# dreamblaster.net
KiCad netlist of a schematic drawn in EAGLE
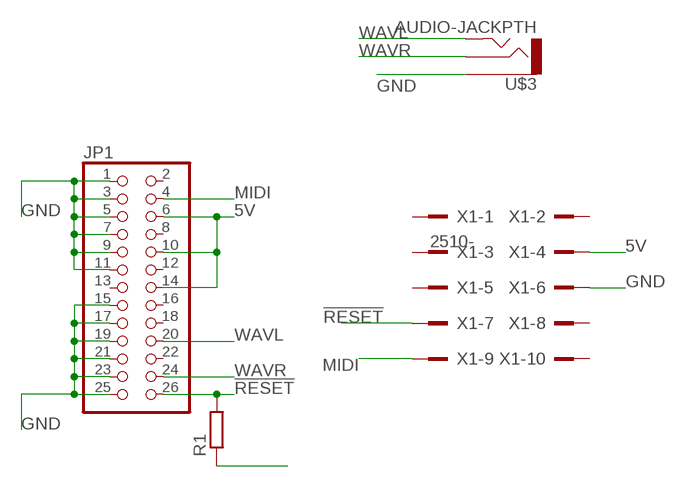
[diagram p0: schematic, sheet 1]

(export (version "E")
  (design (tool "Eeschema 10.0.6"))
  (components
    (comp (ref "JP1")
      (value "PINHD-2X13")
      (footprint "eagle-import:2X13")
      (libsource (lib "eagle-import") (part "PINHD-2X13"))
    )
    (comp (ref "R1")
      (value "R-EU_0204/7")
      (footprint "eagle-import:0204_7")
      (libsource (lib "eagle-import") (part "R-EU_0204/7"))
    )
    (comp (ref "U$3")
      (value "AUDIO-JACKPTH")
      (footprint "eagle-import:AUDIO-JACK")
      (libsource (lib "eagle-import") (part "AUDIO-JACKPTH"))
    )
    (comp (ref "X1")
      (value "2510-")
      (footprint "eagle-import:PAK100_2500-10")
      (fields (field (name "MF") "3M") (field (name "MPN") "2510-6002UB"))
      (libsource (lib "eagle-import") (part "2510-"))
    )
  )
  (nets
    (net (code "1") (name "/5V") (class "Default")
      (node (ref "JP1") (pin "10") (pinfunction "10_10") (pintype "passive"))
      (node (ref "JP1") (pin "14") (pinfunction "14_14") (pintype "passive"))
      (node (ref "JP1") (pin "6") (pinfunction "6_6") (pintype "passive"))
      (node (ref "R1") (pin "1") (pinfunction "1_1") (pintype "passive"))
      (node (ref "X1") (pin "4") (pinfunction "KL_4") (pintype "passive"))
    )
    (net (code "2") (name "/GND") (class "Default")
      (node (ref "JP1") (pin "1") (pinfunction "1_1") (pintype "passive"))
      (node (ref "JP1") (pin "11") (pinfunction "11_11") (pintype "passive"))
      (node (ref "JP1") (pin "15") (pinfunction "15_15") (pintype "passive"))
      (node (ref "JP1") (pin "17") (pinfunction "17_17") (pintype "passive"))
      (node (ref "JP1") (pin "19") (pinfunction "19_19") (pintype "passive"))
      (node (ref "JP1") (pin "21") (pinfunction "21_21") (pintype "passive"))
      (node (ref "JP1") (pin "23") (pinfunction "23_23") (pintype "passive"))
      (node (ref "JP1") (pin "25") (pinfunction "25_25") (pintype "passive"))
      (node (ref "JP1") (pin "3") (pinfunction "3_3") (pintype "passive"))
      (node (ref "JP1") (pin "5") (pinfunction "5_5") (pintype "passive"))
      (node (ref "JP1") (pin "7") (pinfunction "7_7") (pintype "passive"))
      (node (ref "JP1") (pin "9") (pinfunction "9_9") (pintype "passive"))
      (node (ref "U$3") (pin "1") (pinfunction "1_1") (pintype "bidirectional"))
      (node (ref "X1") (pin "6") (pinfunction "KL_6") (pintype "passive"))
    )
    (net (code "3") (name "/MIDI") (class "Default")
      (node (ref "JP1") (pin "4") (pinfunction "4_4") (pintype "passive"))
      (node (ref "X1") (pin "9") (pinfunction "KL_9") (pintype "passive"))
    )
    (net (code "4") (name "/WAVL") (class "Default")
      (node (ref "JP1") (pin "20") (pinfunction "20_20") (pintype "passive"))
      (node (ref "U$3") (pin "5") (pinfunction "5_5") (pintype "bidirectional"))
    )
    (net (code "5") (name "/WAVR") (class "Default")
      (node (ref "JP1") (pin "24") (pinfunction "24_24") (pintype "passive"))
      (node (ref "U$3") (pin "2") (pinfunction "2_2") (pintype "bidirectional"))
    )
    (net (code "6") (name "/~{RESET}") (class "Default")
      (node (ref "JP1") (pin "26") (pinfunction "26_26") (pintype "passive"))
      (node (ref "R1") (pin "2") (pinfunction "2_2") (pintype "passive"))
      (node (ref "X1") (pin "7") (pinfunction "KL_7") (pintype "passive"))
    )
    (net (code "7") (name "unconnected-(JP1-Pad2)") (class "Default")
      (node (ref "JP1") (pin "2") (pinfunction "2_2") (pintype "passive"))
    )
    (net (code "8") (name "unconnected-(JP1-Pad8)") (class "Default")
      (node (ref "JP1") (pin "8") (pinfunction "8_8") (pintype "passive"))
    )
    (net (code "9") (name "unconnected-(JP1-Pad12)") (class "Default")
      (node (ref "JP1") (pin "12") (pinfunction "12_12") (pintype "passive"))
    )
    (net (code "10") (name "unconnected-(JP1-Pad13)") (class "Default")
      (node (ref "JP1") (pin "13") (pinfunction "13_13") (pintype "passive"))
    )
    (net (code "11") (name "unconnected-(JP1-Pad16)") (class "Default")
      (node (ref "JP1") (pin "16") (pinfunction "16_16") (pintype "passive"))
    )
    (net (code "12") (name "unconnected-(JP1-Pad18)") (class "Default")
      (node (ref "JP1") (pin "18") (pinfunction "18_18") (pintype "passive"))
    )
    (net (code "13") (name "unconnected-(JP1-Pad22)") (class "Default")
      (node (ref "JP1") (pin "22") (pinfunction "22_22") (pintype "passive"))
    )
    (net (code "14") (name "unconnected-(X1A-KL-Pad1)") (class "Default")
      (node (ref "X1") (pin "1") (pinfunction "KL_1") (pintype "passive"))
    )
    (net (code "15") (name "unconnected-(X1B-KL-Pad10)") (class "Default")
      (node (ref "X1") (pin "10") (pinfunction "KL_10") (pintype "passive"))
    )
    (net (code "16") (name "unconnected-(X1C-KL-Pad2)") (class "Default")
      (node (ref "X1") (pin "2") (pinfunction "KL_2") (pintype "passive"))
    )
    (net (code "17") (name "unconnected-(X1D-KL-Pad3)") (class "Default")
      (node (ref "X1") (pin "3") (pinfunction "KL_3") (pintype "passive"))
    )
    (net (code "18") (name "unconnected-(X1F-KL-Pad5)") (class "Default")
      (node (ref "X1") (pin "5") (pinfunction "KL_5") (pintype "passive"))
    )
    (net (code "19") (name "unconnected-(X1I-KL-Pad8)") (class "Default")
      (node (ref "X1") (pin "8") (pinfunction "KL_8") (pintype "passive"))
    )
  )
)
